# Neopixels.net
KiCad netlist of a schematic drawn in Altium Designer
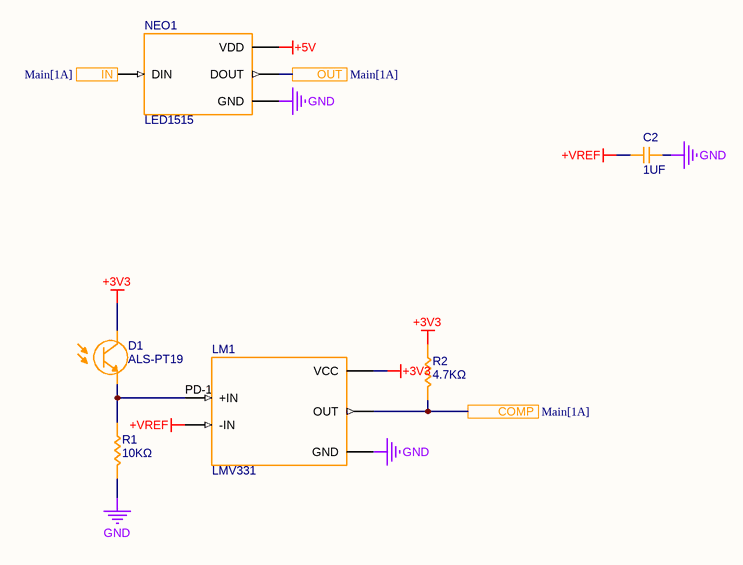
[diagram p0: Neopixels.SchDoc]

(export (version "E")
  (design (tool "Eeschema 10.0.6"))
  (components
    (comp (ref "C2")
      (value "1UF")
      (footprint "CAP_0603")
      (description "Capacitor SMD 0603 generic")
      (libsource (lib "RC") (part "CAP_0603"))
    )
    (comp (ref "D1") (value "ALS-PT19") (footprint "ALS-PT19") (libsource (lib "RC") (part "ALS-PT19")))
    (comp (ref "LM1") (value "LMV331") (footprint "LMV331") (libsource (lib "RC") (part "LMV331")))
    (comp (ref "NEO1") (value "LED1515") (footprint "LED1515") (libsource (lib "RC") (part "LED1515")))
    (comp (ref "R1")
      (value "10KΩ")
      (footprint "RES_0603")
      (description "Resistor SMD 0603 generic")
      (libsource (lib "GenericRC") (part "RES_0603"))
    )
    (comp (ref "R2")
      (value "4.7KΩ")
      (footprint "RES_0603")
      (description "Resistor SMD 0603 generic")
      (libsource (lib "GenericRC") (part "RES_0603"))
    )
  )
  (nets
    (net (code "1") (name "+3V3") (class "Default")
      (node (ref "D1") (pin "C") (pinfunction "C_C") (pintype "passive"))
      (node (ref "LM1") (pin "5") (pinfunction "VCC_5") (pintype "power_in"))
      (node (ref "R2") (pin "2") (pintype "passive"))
    )
    (net (code "2") (name "+5V") (class "Default")
      (node (ref "NEO1") (pin "VDD") (pinfunction "VDD_VDD") (pintype "power_in"))
    )
    (net (code "3") (name "+VREF") (class "Default")
      (node (ref "C2") (pin "2") (pintype "passive"))
      (node (ref "LM1") (pin "3") (pinfunction "-IN_3") (pintype "input"))
    )
    (net (code "4") (name "/COMP") (class "Default")
      (node (ref "LM1") (pin "4") (pinfunction "OUT_4") (pintype "output"))
      (node (ref "R2") (pin "1") (pintype "passive"))
    )
    (net (code "5") (name "/IN") (class "Default")
      (node (ref "NEO1") (pin "DIN") (pinfunction "DIN_DIN") (pintype "input"))
    )
    (net (code "6") (name "/OUT") (class "Default")
      (node (ref "NEO1") (pin "DOUT") (pinfunction "DOUT_DOUT") (pintype "output"))
    )
    (net (code "7") (name "/PD-1") (class "Default")
      (node (ref "D1") (pin "E") (pinfunction "E_E") (pintype "passive"))
      (node (ref "LM1") (pin "1") (pinfunction "+IN_1") (pintype "input"))
      (node (ref "R1") (pin "2") (pintype "passive"))
    )
    (net (code "8") (name "GND") (class "Default")
      (node (ref "C2") (pin "1") (pintype "passive"))
      (node (ref "LM1") (pin "2") (pinfunction "GND_2") (pintype "power_in"))
      (node (ref "NEO1") (pin "GND") (pinfunction "GND_GND") (pintype "power_in"))
      (node (ref "R1") (pin "1") (pintype "passive"))
    )
  )
)
